# Connectors.net
KiCad netlist of a schematic drawn in Altium Designer
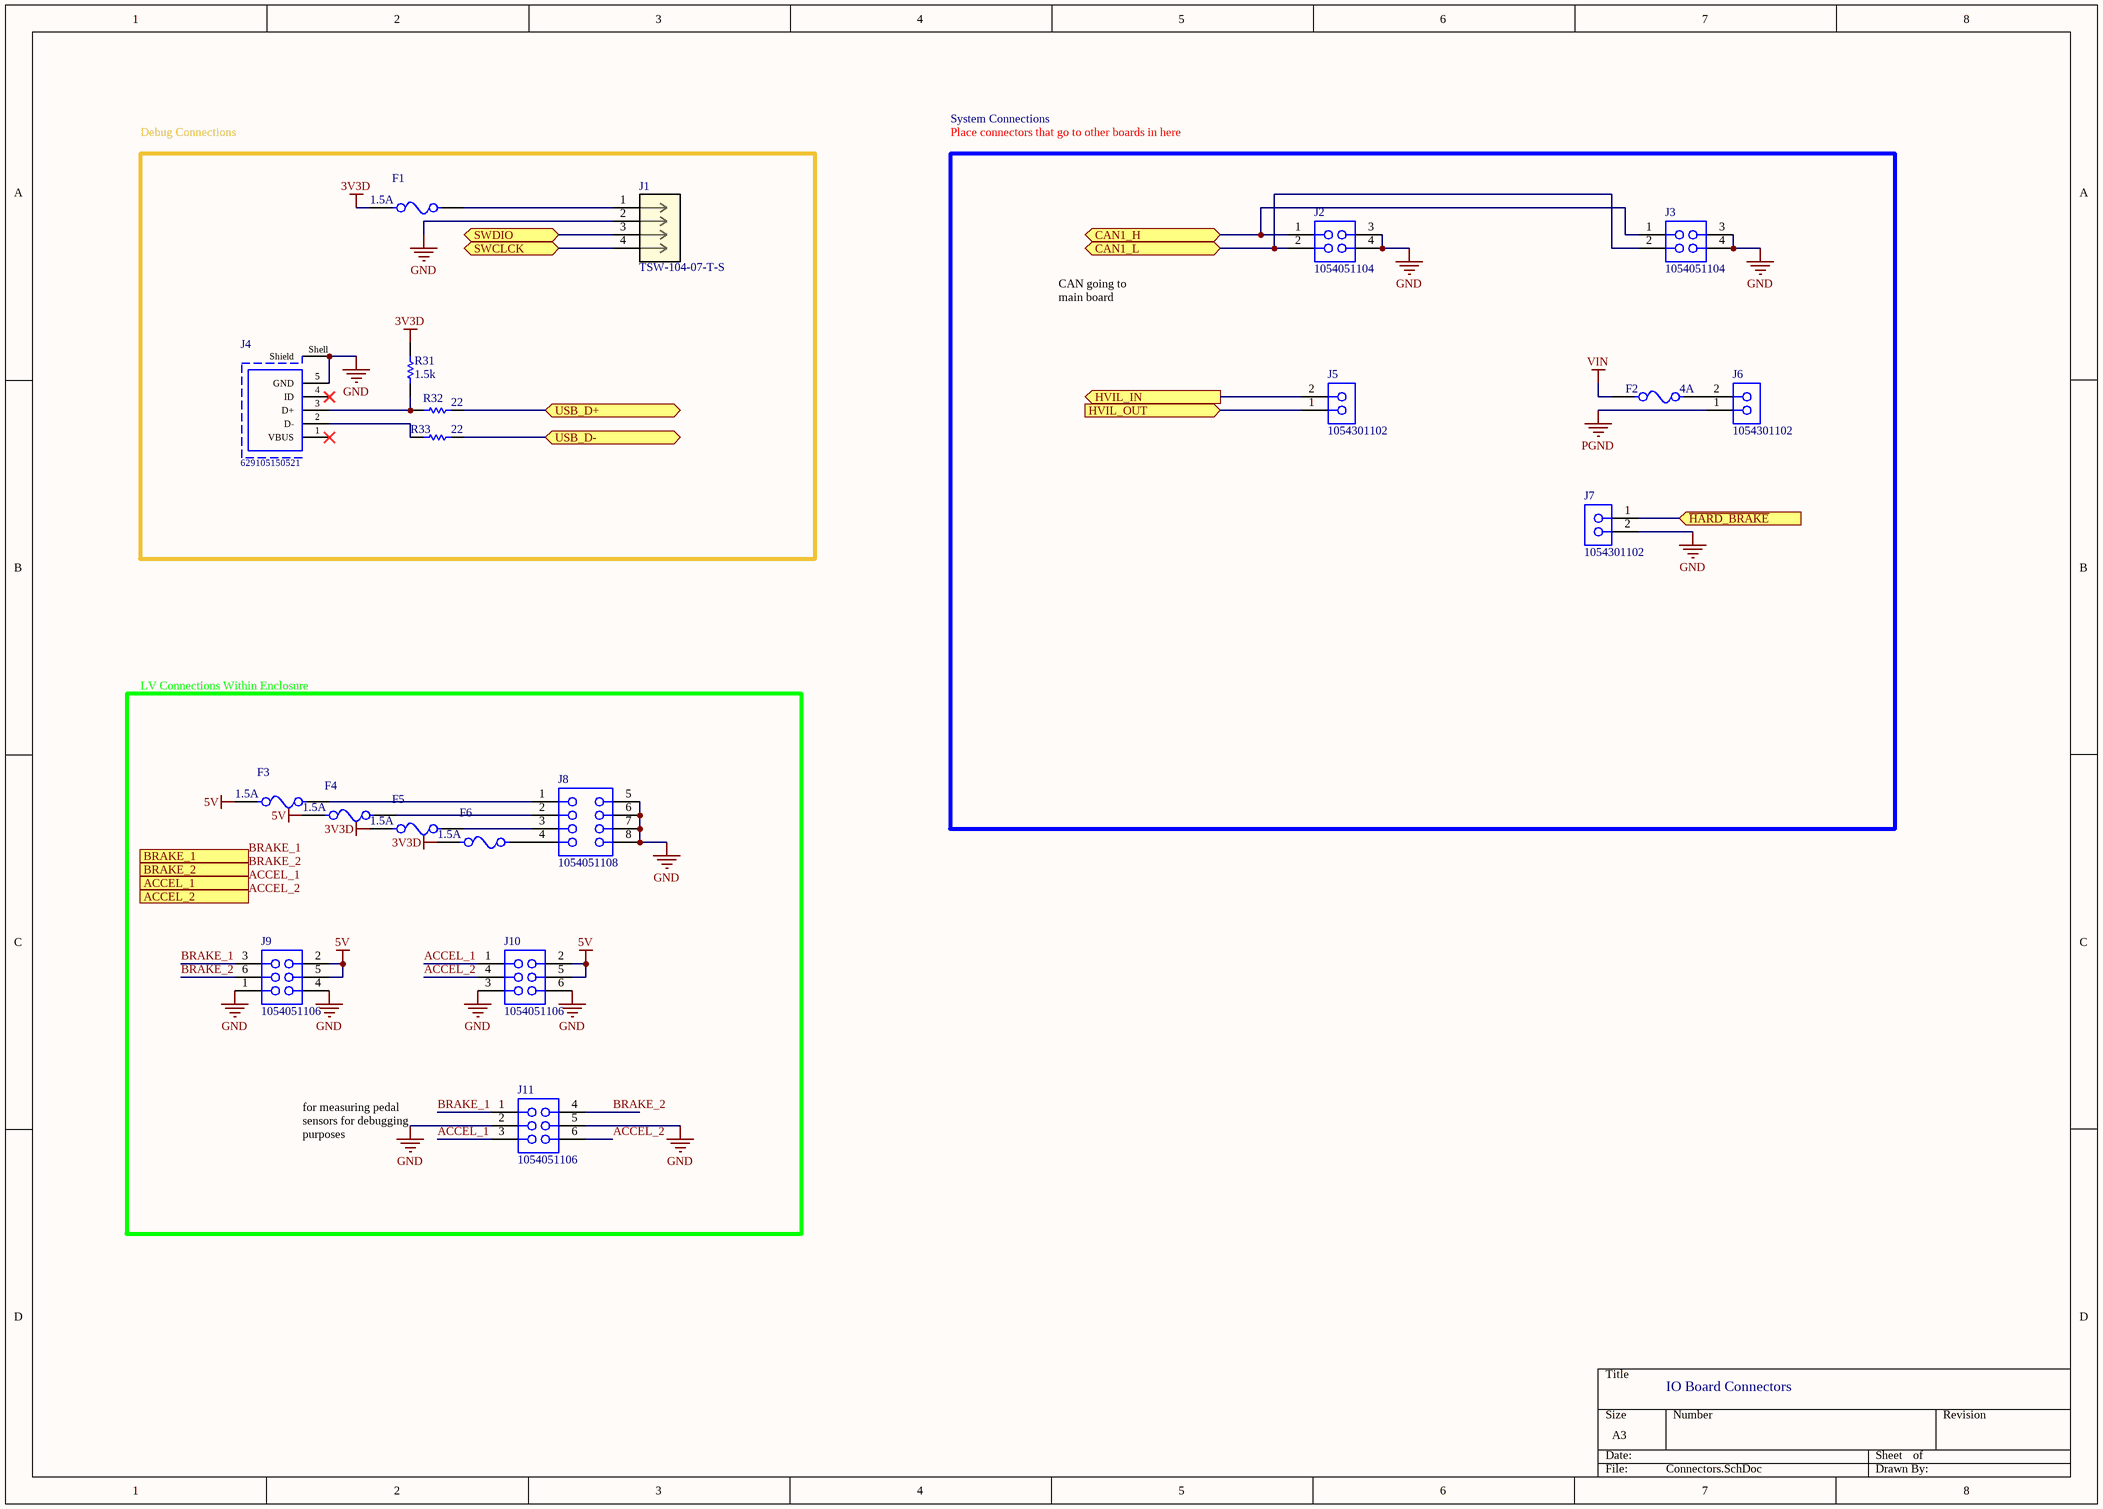
[diagram p0: Connectors.SchDoc]

(export (version "E")
  (design (tool "Eeschema 10.0.6"))
  (components
    (comp (ref "F1")
      (value "1.5A")
      (footprint "FUSC1608X43N")
      (description "1.5A 0603 Fuse")
      (fields
        (field (name "MANUFACTURER_PART_NUMBER") "046701.5NR")
        (field (name "MOUSER PART NUMBER") "576-046701.5NR")
      )
      (libsource (lib "uControllerTemplate2021") (part "046701.5NR"))
    )
    (comp (ref "F2")
      (value "4A")
      (footprint "uControllerTemplate2021:0466004.NR")
      (description "FUSE BOARD MNT 4A 32VAC/VDC 1206")
      (fields
        (field (name "MANUFACTURER") "Littelfuse")
        (field (name "MANUFACTURER PART NUMBER") "0466004.NR")
      )
      (libsource (lib "uControllerTemplate2021") (part "0466004.NR"))
    )
    (comp (ref "F3")
      (value "1.5A")
      (footprint "FUSC1608X43N")
      (description "1.5A 0603 Fuse")
      (fields
        (field (name "MANUFACTURER_PART_NUMBER") "046701.5NR")
        (field (name "MOUSER PART NUMBER") "576-046701.5NR")
      )
      (libsource (lib "uControllerTemplate2021") (part "046701.5NR"))
    )
    (comp (ref "F4")
      (value "1.5A")
      (footprint "FUSC1608X43N")
      (description "1.5A 0603 Fuse")
      (fields
        (field (name "MANUFACTURER_PART_NUMBER") "046701.5NR")
        (field (name "MOUSER PART NUMBER") "576-046701.5NR")
      )
      (libsource (lib "uControllerTemplate2021") (part "046701.5NR"))
    )
    (comp (ref "F5")
      (value "1.5A")
      (footprint "FUSC1608X43N")
      (description "1.5A 0603 Fuse")
      (fields
        (field (name "MANUFACTURER_PART_NUMBER") "046701.5NR")
        (field (name "MOUSER PART NUMBER") "576-046701.5NR")
      )
      (libsource (lib "uControllerTemplate2021") (part "046701.5NR"))
    )
    (comp (ref "F6")
      (value "1.5A")
      (footprint "FUSC1608X43N")
      (description "1.5A 0603 Fuse")
      (fields
        (field (name "MANUFACTURER_PART_NUMBER") "046701.5NR")
        (field (name "MOUSER PART NUMBER") "576-046701.5NR")
      )
      (libsource (lib "uControllerTemplate2021") (part "046701.5NR"))
    )
    (comp (ref "J1")
      (value "TSW-104-07-T-S")
      (footprint "CON4_1X4_TU_TSW")
      (description "4 Pin Header")
      (fields (field (name "COPYRIGHT") "Copyright (C) 2018 Accelerated Designs. All rights reserved"))
      (libsource (lib "uControllerTemplate2021") (part "TSW-104-07-T-S"))
    )
    (comp (ref "J2")
      (value "1054051104")
      (footprint "1054051104")
      (fields (field (name "MANUFACTURER") "Molex"))
      (libsource (lib "uControllerTemplate2021") (part "1054051104"))
    )
    (comp (ref "J3")
      (value "1054051104")
      (footprint "1054051104")
      (fields (field (name "MANUFACTURER") "Molex"))
      (libsource (lib "uControllerTemplate2021") (part "1054051104"))
    )
    (comp (ref "J4")
      (value "629105150521")
      (footprint "629105150521")
      (description "Micro USB 2.0 Type B Receptacle WR-COM, Horizontal, SMT, with Pegs, High Current at Pin 1 & Pin 5")
      (fields (field (name "MANUFACTURER") "Wurth Elektronik") (field (name "PUBLISHER") "WurthElektronik"))
      (libsource (lib "Altium Content Vault") (part "WE-USB-5-1SHLD"))
    )
    (comp (ref "J5")
      (value "1054301102")
      (footprint "1054301102")
      (fields (field (name "MANUFACTURER") "Molex"))
      (libsource (lib "uControllerTemplate2021") (part "1054301102"))
    )
    (comp (ref "J6")
      (value "1054301102")
      (footprint "1054301102")
      (fields (field (name "MANUFACTURER") "Molex"))
      (libsource (lib "uControllerTemplate2021") (part "1054301102"))
    )
    (comp (ref "J7")
      (value "1054301102")
      (footprint "1054301102")
      (fields (field (name "MANUFACTURER") "Molex"))
      (libsource (lib "uControllerTemplate2021") (part "1054301102"))
    )
    (comp (ref "J8")
      (value "1054051108")
      (footprint "1054051108")
      (fields (field (name "MANUFACTURER") "Molex") (field (name "PART NUMBER") "1053141108"))
      (libsource (lib "uControllerTemplate2021") (part "1054051108"))
    )
    (comp (ref "J9")
      (value "1054051106")
      (footprint "1054051106")
      (fields (field (name "MANUFACTURER") "Molex"))
      (libsource (lib "") (part "1054051106_2"))
    )
    (comp (ref "J10")
      (value "1054051106")
      (footprint "1054051106")
      (fields (field (name "MANUFACTURER") "Molex"))
      (libsource (lib "") (part "1054051106_1"))
    )
    (comp (ref "J11")
      (value "1054051106")
      (footprint "1054051106")
      (fields (field (name "MANUFACTURER") "Molex"))
      (libsource (lib "uControllerTemplate2021") (part "1054051106"))
    )
    (comp (ref "R31")
      (value "1.5k")
      (footprint "RESC2013X50X35ML15T15")
      (description "Chip Resistor,1.5k Ohm, +/- 1%, 125 mW, -55 to 155 degC, 0805 (2012 Metric)")
      (fields (field (name "TOLERANCE") "1%") (field (name "POWER") "125mW"))
      (libsource (lib "Caltech FSAE") (part "RES-2"))
    )
    (comp (ref "R32")
      (value "22")
      (footprint "RESC0805(2012)_L")
      (description "100K 0.125W 1% 0805 (2012 Metric)  SMD")
      (fields (field (name "TOLERANCE") "1 %") (field (name "POWER") "0.125 W"))
      (libsource (lib "Altium Content Vault") (part "RES"))
    )
    (comp (ref "R33")
      (value "22")
      (footprint "RESC2013X50X35ML15T15")
      (description "Chip Resistor, 22 Ohm, +/- 1%, 125 mW, -55 to 155 degC, 0805 (2012 Metric)")
      (fields (field (name "TOLERANCE") "1%") (field (name "POWER") "125mW"))
      (libsource (lib "Caltech FSAE") (part "RES-2"))
    )
  )
  (nets
    (net (code "1") (name "/ACCEL_1") (class "Default")
      (node (ref "J10") (pin "1") (pinfunction "1_1") (pintype "passive"))
      (node (ref "J11") (pin "3") (pinfunction "3_3") (pintype "passive"))
    )
    (net (code "2") (name "/ACCEL_2") (class "Default")
      (node (ref "J10") (pin "4") (pinfunction "4_4") (pintype "passive"))
      (node (ref "J11") (pin "6") (pinfunction "6_6") (pintype "passive"))
    )
    (net (code "3") (name "/BRAKE_1") (class "Default")
      (node (ref "J11") (pin "1") (pinfunction "1_1") (pintype "passive"))
      (node (ref "J9") (pin "3") (pinfunction "3_3") (pintype "passive"))
    )
    (net (code "4") (name "/BRAKE_2") (class "Default")
      (node (ref "J11") (pin "4") (pinfunction "4_4") (pintype "passive"))
      (node (ref "J9") (pin "6") (pinfunction "6_6") (pintype "passive"))
    )
    (net (code "5") (name "/CAN1_H") (class "Default")
      (node (ref "J2") (pin "1") (pinfunction "1_1") (pintype "passive"))
      (node (ref "J3") (pin "1") (pinfunction "1_1") (pintype "passive"))
    )
    (net (code "6") (name "/CAN1_L") (class "Default")
      (node (ref "J2") (pin "2") (pinfunction "2_2") (pintype "passive"))
      (node (ref "J3") (pin "2") (pinfunction "2_2") (pintype "passive"))
    )
    (net (code "7") (name "/HVIL_IN") (class "Default")
      (node (ref "J5") (pin "2") (pinfunction "2_2") (pintype "passive"))
    )
    (net (code "8") (name "/HVIL_OUT") (class "Default")
      (node (ref "J5") (pin "1") (pinfunction "1_1") (pintype "passive"))
    )
    (net (code "9") (name "/SWCLCK") (class "Default")
      (node (ref "J1") (pin "4") (pinfunction "4_4") (pintype "passive"))
    )
    (net (code "10") (name "/SWDIO") (class "Default")
      (node (ref "J1") (pin "3") (pinfunction "3_3") (pintype "passive"))
    )
    (net (code "11") (name "/USB_D+") (class "Default")
      (node (ref "R32") (pin "1") (pinfunction "1_1") (pintype "passive"))
    )
    (net (code "12") (name "/USB_D-") (class "Default")
      (node (ref "R33") (pin "1") (pinfunction "1_1") (pintype "passive"))
    )
    (net (code "13") (name "/~{HARD_BRAKE}") (class "Default")
      (node (ref "J7") (pin "1") (pinfunction "1_1") (pintype "passive"))
    )
    (net (code "14") (name "3V3D") (class "Default")
      (node (ref "F1") (pin "1") (pinfunction "1_1") (pintype "passive"))
      (node (ref "F5") (pin "1") (pinfunction "1_1") (pintype "passive"))
      (node (ref "F6") (pin "1") (pinfunction "1_1") (pintype "passive"))
      (node (ref "R31") (pin "1") (pinfunction "1_1") (pintype "passive"))
    )
    (net (code "15") (name "5V") (class "Default")
      (node (ref "F3") (pin "1") (pinfunction "1_1") (pintype "passive"))
      (node (ref "F4") (pin "1") (pinfunction "1_1") (pintype "passive"))
      (node (ref "J10") (pin "2") (pinfunction "2_2") (pintype "passive"))
      (node (ref "J10") (pin "5") (pinfunction "5_5") (pintype "passive"))
      (node (ref "J9") (pin "2") (pinfunction "2_2") (pintype "passive"))
      (node (ref "J9") (pin "5") (pinfunction "5_5") (pintype "passive"))
    )
    (net (code "16") (name "GND") (class "Default")
      (node (ref "J1") (pin "2") (pinfunction "2_2") (pintype "passive"))
      (node (ref "J10") (pin "3") (pinfunction "3_3") (pintype "passive"))
      (node (ref "J10") (pin "6") (pinfunction "6_6") (pintype "passive"))
      (node (ref "J11") (pin "2") (pinfunction "2_2") (pintype "passive"))
      (node (ref "J11") (pin "5") (pinfunction "5_5") (pintype "passive"))
      (node (ref "J2") (pin "3") (pinfunction "3_3") (pintype "passive"))
      (node (ref "J2") (pin "4") (pinfunction "4_4") (pintype "passive"))
      (node (ref "J3") (pin "3") (pinfunction "3_3") (pintype "passive"))
      (node (ref "J3") (pin "4") (pinfunction "4_4") (pintype "passive"))
      (node (ref "J4") (pin "5") (pinfunction "GND_5") (pintype "passive"))
      (node (ref "J4") (pin "Shell") (pinfunction "Shield_Shell") (pintype "passive"))
      (node (ref "J7") (pin "2") (pinfunction "2_2") (pintype "passive"))
      (node (ref "J8") (pin "5") (pinfunction "5_5") (pintype "passive"))
      (node (ref "J8") (pin "6") (pinfunction "6_6") (pintype "passive"))
      (node (ref "J8") (pin "7") (pinfunction "7_7") (pintype "passive"))
      (node (ref "J8") (pin "8") (pinfunction "8_8") (pintype "passive"))
      (node (ref "J9") (pin "1") (pinfunction "1_1") (pintype "passive"))
      (node (ref "J9") (pin "4") (pinfunction "4_4") (pintype "passive"))
    )
    (net (code "17") (name "Net-(F1-Pad2)") (class "Default")
      (node (ref "F1") (pin "2") (pinfunction "2_2") (pintype "passive"))
      (node (ref "J1") (pin "1") (pinfunction "1_1") (pintype "passive"))
    )
    (net (code "18") (name "Net-(F2-Pad2)") (class "Default")
      (node (ref "F2") (pin "2") (pinfunction "2_2") (pintype "passive"))
      (node (ref "J6") (pin "2") (pinfunction "2_2") (pintype "passive"))
    )
    (net (code "19") (name "Net-(F3-Pad2)") (class "Default")
      (node (ref "F3") (pin "2") (pinfunction "2_2") (pintype "passive"))
      (node (ref "J8") (pin "1") (pinfunction "1_1") (pintype "passive"))
    )
    (net (code "20") (name "Net-(F4-Pad2)") (class "Default")
      (node (ref "F4") (pin "2") (pinfunction "2_2") (pintype "passive"))
      (node (ref "J8") (pin "2") (pinfunction "2_2") (pintype "passive"))
    )
    (net (code "21") (name "Net-(F5-Pad2)") (class "Default")
      (node (ref "F5") (pin "2") (pinfunction "2_2") (pintype "passive"))
      (node (ref "J8") (pin "3") (pinfunction "3_3") (pintype "passive"))
    )
    (net (code "22") (name "Net-(F6-Pad2)") (class "Default")
      (node (ref "F6") (pin "2") (pinfunction "2_2") (pintype "passive"))
      (node (ref "J8") (pin "4") (pinfunction "4_4") (pintype "passive"))
    )
    (net (code "23") (name "Net-(J4-D+)") (class "Default")
      (node (ref "J4") (pin "3") (pinfunction "D+_3") (pintype "passive"))
      (node (ref "R31") (pin "2") (pinfunction "2_2") (pintype "passive"))
      (node (ref "R32") (pin "2") (pinfunction "2_2") (pintype "passive"))
    )
    (net (code "24") (name "Net-(J4-D-)") (class "Default")
      (node (ref "J4") (pin "2") (pinfunction "D-_2") (pintype "passive"))
      (node (ref "R33") (pin "2") (pinfunction "2_2") (pintype "passive"))
    )
    (net (code "25") (name "PGND") (class "Default")
      (node (ref "J6") (pin "1") (pinfunction "1_1") (pintype "passive"))
    )
    (net (code "26") (name "VIN") (class "Default")
      (node (ref "F2") (pin "1") (pinfunction "1_1") (pintype "passive"))
    )
    (net (code "27") (name "unconnected-(J4-ID-Pad4)") (class "Default")
      (node (ref "J4") (pin "4") (pinfunction "ID_4") (pintype "passive+no_connect"))
    )
    (net (code "28") (name "unconnected-(J4-VBUS-Pad1)") (class "Default")
      (node (ref "J4") (pin "1") (pinfunction "VBUS_1") (pintype "passive+no_connect"))
    )
  )
)
